# main_processor.net
KiCad netlist of a schematic drawn in Altium Designer
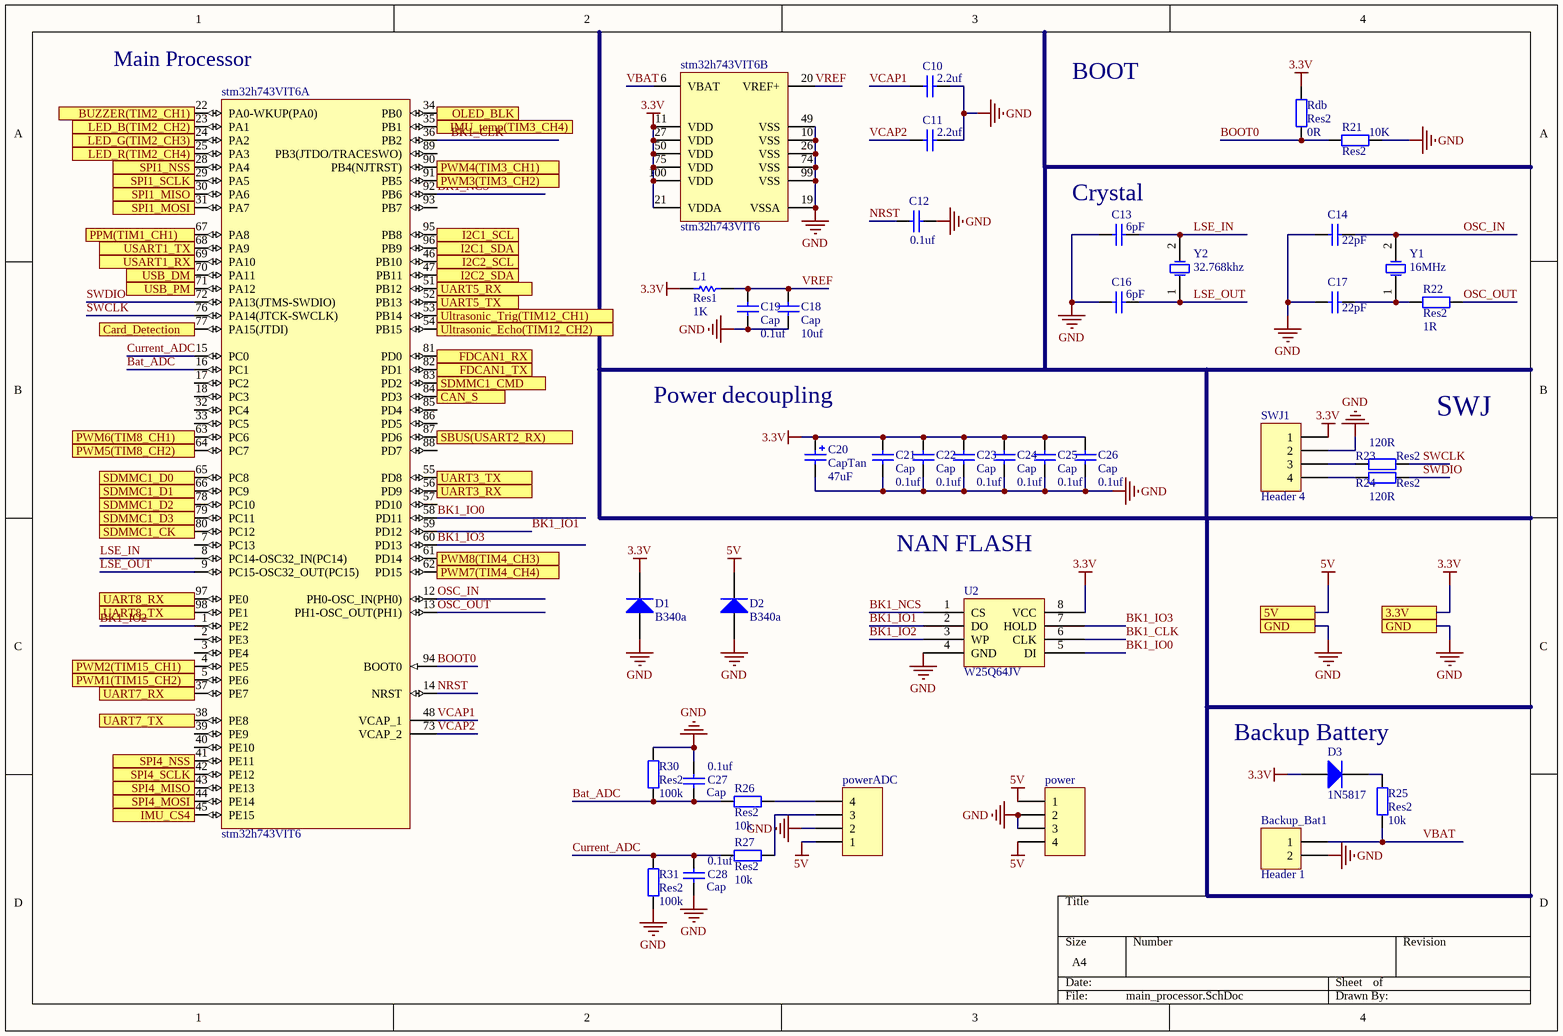
[diagram p0: main_processor.SchDoc]

(export (version "E")
  (design (tool "Eeschema 10.0.6"))
  (components
    (comp (ref "Backup_Bat1")
      (value "Header 1")
      (footprint "Battery-MS621")
      (description "Header, 2-Pin")
      (fields (field (name "PUBLISHER") "Altium Limited"))
      (libsource (lib "Miscellaneous Connectors") (part "Header 2"))
    )
    (comp (ref "C10")
      (value "2.2uf")
      (footprint "0603")
      (description "Capacitor")
      (fields (field (name "Comment") "Cap") (field (name "PUBLISHER") "Altium Limited"))
      (libsource (lib "Miscellaneous Devices") (part "Cap"))
    )
    (comp (ref "C11")
      (value "2.2uf")
      (footprint "0603")
      (description "Capacitor")
      (fields (field (name "Comment") "Cap") (field (name "PUBLISHER") "Altium Limited"))
      (libsource (lib "Miscellaneous Devices") (part "Cap"))
    )
    (comp (ref "C12")
      (value "0.1uf")
      (footprint "0603")
      (description "Capacitor")
      (fields (field (name "Comment") "Cap") (field (name "PUBLISHER") "Altium Limited"))
      (libsource (lib "Miscellaneous Devices") (part "Cap"))
    )
    (comp (ref "C13")
      (value "6pF")
      (footprint "0603")
      (description "Capacitor")
      (fields (field (name "Comment") "Cap") (field (name "PUBLISHER") "Altium Limited"))
      (libsource (lib "Miscellaneous Devices") (part "Cap"))
    )
    (comp (ref "C14")
      (value "22pF")
      (footprint "0603")
      (description "Capacitor")
      (fields (field (name "Comment") "Cap") (field (name "PUBLISHER") "Altium Limited"))
      (libsource (lib "Miscellaneous Devices") (part "Cap"))
    )
    (comp (ref "C16")
      (value "6pF")
      (footprint "0603")
      (description "Capacitor")
      (fields (field (name "Comment") "Cap") (field (name "PUBLISHER") "Altium Limited"))
      (libsource (lib "Miscellaneous Devices") (part "Cap"))
    )
    (comp (ref "C17")
      (value "22pF")
      (footprint "0603")
      (description "Capacitor")
      (fields (field (name "Comment") "Cap") (field (name "PUBLISHER") "Altium Limited"))
      (libsource (lib "Miscellaneous Devices") (part "Cap"))
    )
    (comp (ref "C18")
      (value "Cap")
      (footprint "0603")
      (description "Capacitor")
      (fields (field (name "ALTIUM_VALUE") "10uf") (field (name "PUBLISHER") "Altium Limited"))
      (libsource (lib "Miscellaneous Devices") (part "Cap"))
    )
    (comp (ref "C19")
      (value "Cap")
      (footprint "0603")
      (description "Capacitor")
      (fields (field (name "ALTIUM_VALUE") "0.1uf") (field (name "PUBLISHER") "Altium Limited"))
      (libsource (lib "Miscellaneous Devices") (part "Cap"))
    )
    (comp (ref "C20")
      (value "CapTan")
      (footprint "1206_P")
      (description "Polarized Capacitor (Axial)")
      (fields (field (name "ALTIUM_VALUE") "47uF") (field (name "PUBLISHER") "Altium Limited"))
      (libsource (lib "Miscellaneous Devices") (part "Cap Pol2"))
    )
    (comp (ref "C21")
      (value "Cap")
      (footprint "0603")
      (description "Capacitor")
      (fields (field (name "ALTIUM_VALUE") "0.1uf") (field (name "PUBLISHER") "Altium Limited"))
      (libsource (lib "Miscellaneous Devices") (part "Cap"))
    )
    (comp (ref "C22")
      (value "Cap")
      (footprint "0603")
      (description "Capacitor")
      (fields (field (name "ALTIUM_VALUE") "0.1uf") (field (name "PUBLISHER") "Altium Limited"))
      (libsource (lib "Miscellaneous Devices") (part "Cap"))
    )
    (comp (ref "C23")
      (value "Cap")
      (footprint "0603")
      (description "Capacitor")
      (fields (field (name "ALTIUM_VALUE") "0.1uf") (field (name "PUBLISHER") "Altium Limited"))
      (libsource (lib "Miscellaneous Devices") (part "Cap"))
    )
    (comp (ref "C24")
      (value "Cap")
      (footprint "0603")
      (description "Capacitor")
      (fields (field (name "ALTIUM_VALUE") "0.1uf") (field (name "PUBLISHER") "Altium Limited"))
      (libsource (lib "Miscellaneous Devices") (part "Cap"))
    )
    (comp (ref "C25")
      (value "Cap")
      (footprint "0603")
      (description "Capacitor")
      (fields (field (name "ALTIUM_VALUE") "0.1uf") (field (name "PUBLISHER") "Altium Limited"))
      (libsource (lib "Miscellaneous Devices") (part "Cap"))
    )
    (comp (ref "C26")
      (value "Cap")
      (footprint "0603")
      (description "Capacitor")
      (fields (field (name "ALTIUM_VALUE") "0.1uf") (field (name "PUBLISHER") "Altium Limited"))
      (libsource (lib "Miscellaneous Devices") (part "Cap"))
    )
    (comp (ref "C27")
      (value "Cap")
      (footprint "0603")
      (description "Capacitor")
      (fields (field (name "ALTIUM_VALUE") "0.1uf") (field (name "PUBLISHER") "Altium Limited"))
      (libsource (lib "Miscellaneous Devices") (part "Cap"))
    )
    (comp (ref "C28")
      (value "Cap")
      (footprint "0603")
      (description "Capacitor")
      (fields (field (name "ALTIUM_VALUE") "0.1uf") (field (name "PUBLISHER") "Altium Limited"))
      (libsource (lib "Miscellaneous Devices") (part "Cap"))
    )
    (comp (ref "D1")
      (value "B340a")
      (footprint "DO_214_AC")
      (description "Default Diode")
      (fields (field (name "PUBLISHER") "Altium Limited"))
      (libsource (lib "Miscellaneous Devices") (part "Diode"))
    )
    (comp (ref "D2")
      (value "B340a")
      (footprint "DO_214_AC")
      (description "Default Diode")
      (fields (field (name "PUBLISHER") "Altium Limited"))
      (libsource (lib "Miscellaneous Devices") (part "Diode"))
    )
    (comp (ref "D3")
      (value "1N5817")
      (footprint "SOD323")
      (description "Default Diode")
      (fields (field (name "PUBLISHER") "Altium Limited"))
      (libsource (lib "Miscellaneous Devices") (part "Diode"))
    )
    (comp (ref "L1")
      (value "Res1")
      (footprint "AXIAL-0.3")
      (description "Resistor")
      (fields (field (name "ALTIUM_VALUE") "1K") (field (name "PUBLISHER") "Altium Limited"))
      (libsource (lib "Miscellaneous Devices") (part "Res1"))
    )
    (comp (ref "power")
      (value "Header 2")
      (footprint "SH_1.25mm_LT_4P")
      (description "Header, 4-Pin")
      (fields (field (name "PUBLISHER") "Altium Limited"))
      (libsource (lib "") (part "Header 4_1"))
    )
    (comp (ref "powerADC")
      (value "Header 2")
      (footprint "SH_1.25mm_LT_4P")
      (description "Header, 4-Pin")
      (fields (field (name "PUBLISHER") "Altium Limited"))
      (libsource (lib "") (part "Header 4_2"))
    )
    (comp (ref "R21")
      (value "Res2")
      (footprint "0603")
      (description "Resistor")
      (fields (field (name "ALTIUM_VALUE") "10K") (field (name "PUBLISHER") "Altium Limited"))
      (libsource (lib "") (part "Res2_3"))
    )
    (comp (ref "R22")
      (value "Res2")
      (footprint "0603")
      (description "Resistor")
      (fields (field (name "ALTIUM_VALUE") "1R") (field (name "PUBLISHER") "Altium Limited"))
      (libsource (lib "Miscellaneous Devices") (part "Res2"))
    )
    (comp (ref "R23")
      (value "Res2")
      (footprint "0603")
      (description "Resistor")
      (fields (field (name "ALTIUM_VALUE") "120R") (field (name "PUBLISHER") "Altium Limited"))
      (libsource (lib "") (part "Res2_1"))
    )
    (comp (ref "R24")
      (value "Res2")
      (footprint "0603")
      (description "Resistor")
      (fields (field (name "ALTIUM_VALUE") "120R") (field (name "PUBLISHER") "Altium Limited"))
      (libsource (lib "") (part "Res2_1"))
    )
    (comp (ref "R25")
      (value "Res2")
      (footprint "0603")
      (description "Resistor")
      (fields (field (name "ALTIUM_VALUE") "10k") (field (name "PUBLISHER") "Altium Limited"))
      (libsource (lib "Miscellaneous Devices") (part "Res2"))
    )
    (comp (ref "R26")
      (value "Res2")
      (footprint "0603")
      (description "Resistor")
      (fields (field (name "ALTIUM_VALUE") "10k") (field (name "PUBLISHER") "Altium Limited"))
      (libsource (lib "") (part "Res2_1"))
    )
    (comp (ref "R27")
      (value "Res2")
      (footprint "0603")
      (description "Resistor")
      (fields (field (name "ALTIUM_VALUE") "10k") (field (name "PUBLISHER") "Altium Limited"))
      (libsource (lib "") (part "Res2_1"))
    )
    (comp (ref "R30")
      (value "Res2")
      (footprint "0603")
      (description "Resistor")
      (fields (field (name "ALTIUM_VALUE") "100k") (field (name "PUBLISHER") "Altium Limited"))
      (libsource (lib "Miscellaneous Devices") (part "Res2"))
    )
    (comp (ref "R31")
      (value "Res2")
      (footprint "0603")
      (description "Resistor")
      (fields (field (name "ALTIUM_VALUE") "100k") (field (name "PUBLISHER") "Altium Limited"))
      (libsource (lib "Miscellaneous Devices") (part "Res2"))
    )
    (comp (ref "Rdb")
      (value "Res2")
      (footprint "0603")
      (description "Resistor")
      (fields (field (name "ALTIUM_VALUE") "0R") (field (name "PUBLISHER") "Altium Limited"))
      (libsource (lib "") (part "Res2_2"))
    )
    (comp (ref "stm32h743VIT6")
      (value "stm32h743VIT6")
      (footprint "LQFP100-14x14mm")
      (libsource (lib "SchlibProcessor") (part "stm32h743VIT6"))
    )
    (comp (ref "SWJ1")
      (value "Header 4")
      (footprint "SH_1.25mm_LT_4P")
      (description "Header, 4-Pin")
      (fields (field (name "PUBLISHER") "Altium Limited"))
      (libsource (lib "Miscellaneous Connectors") (part "Header 4"))
    )
    (comp (ref "U2")
      (value "W25Q64JV")
      (footprint "W25Q SOP8")
      (libsource (lib "SchlibDevices") (part "W25Q64JV"))
    )
    (comp (ref "Y1")
      (value "16MHz")
      (footprint "Crystal_SMD_3225")
      (description "Crystal Oscillator")
      (fields (field (name "PUBLISHER") "Altium Limited"))
      (libsource (lib "Explorer STM32F407封装库") (part "XTAL"))
    )
    (comp (ref "Y2")
      (value "32.768khz")
      (footprint "FC135")
      (description "Crystal Oscillator")
      (fields (field (name "PUBLISHER") "Altium Limited"))
      (libsource (lib "Explorer STM32F407封装库") (part "XTAL"))
    )
  )
  (nets
    (net (code "1") (name "/BK1_CLK") (class "Default")
      (node (ref "U2") (pin "6") (pinfunction "CLK_6") (pintype "passive"))
      (node (ref "stm32h743VIT6") (pin "36") (pinfunction "PB2_36") (pintype "bidirectional"))
    )
    (net (code "2") (name "/BK1_IO0") (class "Default")
      (node (ref "U2") (pin "5") (pinfunction "DI_5") (pintype "passive"))
      (node (ref "stm32h743VIT6") (pin "58") (pinfunction "PD11_58") (pintype "bidirectional"))
    )
    (net (code "3") (name "/BK1_IO1") (class "Default")
      (node (ref "U2") (pin "2") (pinfunction "DO_2") (pintype "passive"))
      (node (ref "stm32h743VIT6") (pin "59") (pinfunction "PD12_59") (pintype "bidirectional"))
    )
    (net (code "4") (name "/BK1_IO2") (class "Default")
      (node (ref "U2") (pin "3") (pinfunction "WP_3") (pintype "passive"))
      (node (ref "stm32h743VIT6") (pin "1") (pinfunction "PE2_1") (pintype "bidirectional"))
    )
    (net (code "5") (name "/BK1_IO3") (class "Default")
      (node (ref "U2") (pin "7") (pinfunction "HOLD_7") (pintype "passive"))
      (node (ref "stm32h743VIT6") (pin "60") (pinfunction "PD13_60") (pintype "bidirectional"))
    )
    (net (code "6") (name "/BK1_NCS") (class "Default")
      (node (ref "U2") (pin "1") (pinfunction "CS_1") (pintype "passive"))
      (node (ref "stm32h743VIT6") (pin "92") (pinfunction "PB6_92") (pintype "bidirectional"))
    )
    (net (code "7") (name "/BOOT0") (class "Default")
      (node (ref "R21") (pin "1") (pinfunction "1_1") (pintype "passive"))
      (node (ref "Rdb") (pin "1") (pinfunction "1_1") (pintype "passive"))
      (node (ref "stm32h743VIT6") (pin "94") (pinfunction "BOOT0_94") (pintype "input"))
    )
    (net (code "8") (name "/BUZZER(TIM2_CH1)") (class "Default")
      (node (ref "stm32h743VIT6") (pin "22") (pinfunction "PA0-WKUP(PA0)_22") (pintype "bidirectional"))
    )
    (net (code "9") (name "/Bat_ADC") (class "Default")
      (node (ref "C27") (pin "1") (pinfunction "1_1") (pintype "passive"))
      (node (ref "R26") (pin "2") (pinfunction "2_2") (pintype "passive"))
      (node (ref "R30") (pin "2") (pinfunction "2_2") (pintype "passive"))
      (node (ref "stm32h743VIT6") (pin "16") (pinfunction "PC1_16") (pintype "bidirectional"))
    )
    (net (code "10") (name "/CAN_S") (class "Default")
      (node (ref "stm32h743VIT6") (pin "84") (pinfunction "PD3_84") (pintype "bidirectional"))
    )
    (net (code "11") (name "/Card_Detection") (class "Default")
      (node (ref "stm32h743VIT6") (pin "77") (pinfunction "PA15(JTDI)_77") (pintype "bidirectional"))
    )
    (net (code "12") (name "/Current_ADC") (class "Default")
      (node (ref "C28") (pin "2") (pinfunction "2_2") (pintype "passive"))
      (node (ref "R27") (pin "2") (pinfunction "2_2") (pintype "passive"))
      (node (ref "R31") (pin "1") (pinfunction "1_1") (pintype "passive"))
      (node (ref "stm32h743VIT6") (pin "15") (pinfunction "PC0_15") (pintype "bidirectional"))
    )
    (net (code "13") (name "/FDCAN1_RX") (class "Default")
      (node (ref "stm32h743VIT6") (pin "81") (pinfunction "PD0_81") (pintype "bidirectional"))
    )
    (net (code "14") (name "/FDCAN1_TX") (class "Default")
      (node (ref "stm32h743VIT6") (pin "82") (pinfunction "PD1_82") (pintype "bidirectional"))
    )
    (net (code "15") (name "/I2C1_SCL") (class "Default")
      (node (ref "stm32h743VIT6") (pin "95") (pinfunction "PB8_95") (pintype "bidirectional"))
    )
    (net (code "16") (name "/I2C1_SDA") (class "Default")
      (node (ref "stm32h743VIT6") (pin "96") (pinfunction "PB9_96") (pintype "bidirectional"))
    )
    (net (code "17") (name "/I2C2_SCL") (class "Default")
      (node (ref "stm32h743VIT6") (pin "46") (pinfunction "PB10_46") (pintype "bidirectional"))
    )
    (net (code "18") (name "/I2C2_SDA") (class "Default")
      (node (ref "stm32h743VIT6") (pin "47") (pinfunction "PB11_47") (pintype "bidirectional"))
    )
    (net (code "19") (name "/IMU_CS4") (class "Default")
      (node (ref "stm32h743VIT6") (pin "45") (pinfunction "PE15_45") (pintype "bidirectional"))
    )
    (net (code "20") (name "/IMU_temp(TIM3_CH4)") (class "Default")
      (node (ref "stm32h743VIT6") (pin "35") (pinfunction "PB1_35") (pintype "bidirectional"))
    )
    (net (code "21") (name "/LED_B(TIM2_CH2)") (class "Default")
      (node (ref "stm32h743VIT6") (pin "23") (pinfunction "PA1_23") (pintype "bidirectional"))
    )
    (net (code "22") (name "/LED_G(TIM2_CH3)") (class "Default")
      (node (ref "stm32h743VIT6") (pin "24") (pinfunction "PA2_24") (pintype "bidirectional"))
    )
    (net (code "23") (name "/LED_R(TIM2_CH4)") (class "Default")
      (node (ref "stm32h743VIT6") (pin "25") (pinfunction "PA3_25") (pintype "bidirectional"))
    )
    (net (code "24") (name "/LSE_IN") (class "Default")
      (node (ref "C13") (pin "2") (pinfunction "2_2") (pintype "passive"))
      (node (ref "Y2") (pin "2") (pinfunction "OSC2_2") (pintype "passive"))
      (node (ref "stm32h743VIT6") (pin "8") (pinfunction "PC14-OSC32_IN(PC14)_8") (pintype "bidirectional"))
    )
    (net (code "25") (name "/LSE_OUT") (class "Default")
      (node (ref "C16") (pin "2") (pinfunction "2_2") (pintype "passive"))
      (node (ref "Y2") (pin "1") (pinfunction "OSC1_1") (pintype "passive"))
      (node (ref "stm32h743VIT6") (pin "9") (pinfunction "PC15-OSC32_OUT(PC15)_9") (pintype "bidirectional"))
    )
    (net (code "26") (name "/NRST") (class "Default")
      (node (ref "C12") (pin "2") (pinfunction "2_2") (pintype "passive"))
      (node (ref "stm32h743VIT6") (pin "14") (pinfunction "NRST_14") (pintype "bidirectional"))
    )
    (net (code "27") (name "/OLED_BLK") (class "Default")
      (node (ref "stm32h743VIT6") (pin "34") (pinfunction "PB0_34") (pintype "bidirectional"))
    )
    (net (code "28") (name "/OSC_IN") (class "Default")
      (node (ref "C14") (pin "2") (pinfunction "2_2") (pintype "passive"))
      (node (ref "Y1") (pin "2") (pinfunction "OSC2_2") (pintype "passive"))
      (node (ref "stm32h743VIT6") (pin "12") (pinfunction "PH0-OSC_IN(PH0)_12") (pintype "bidirectional"))
    )
    (net (code "29") (name "/OSC_OUT") (class "Default")
      (node (ref "R22") (pin "1") (pinfunction "1_1") (pintype "passive"))
      (node (ref "stm32h743VIT6") (pin "13") (pinfunction "PH1-OSC_OUT(PH1)_13") (pintype "bidirectional"))
    )
    (net (code "30") (name "/PPM(TIM1_CH1)") (class "Default")
      (node (ref "stm32h743VIT6") (pin "67") (pinfunction "PA8_67") (pintype "bidirectional"))
    )
    (net (code "31") (name "/PWM1(TIM15_CH2)") (class "Default")
      (node (ref "stm32h743VIT6") (pin "5") (pinfunction "PE6_5") (pintype "bidirectional"))
    )
    (net (code "32") (name "/PWM2(TIM15_CH1)") (class "Default")
      (node (ref "stm32h743VIT6") (pin "4") (pinfunction "PE5_4") (pintype "bidirectional"))
    )
    (net (code "33") (name "/PWM3(TIM3_CH2)") (class "Default")
      (node (ref "stm32h743VIT6") (pin "91") (pinfunction "PB5_91") (pintype "bidirectional"))
    )
    (net (code "34") (name "/PWM4(TIM3_CH1)") (class "Default")
      (node (ref "stm32h743VIT6") (pin "90") (pinfunction "PB4(NJTRST)_90") (pintype "bidirectional"))
    )
    (net (code "35") (name "/PWM5(TIM8_CH2)") (class "Default")
      (node (ref "stm32h743VIT6") (pin "64") (pinfunction "PC7_64") (pintype "bidirectional"))
    )
    (net (code "36") (name "/PWM6(TIM8_CH1)") (class "Default")
      (node (ref "stm32h743VIT6") (pin "63") (pinfunction "PC6_63") (pintype "bidirectional"))
    )
    (net (code "37") (name "/PWM7(TIM4_CH4)") (class "Default")
      (node (ref "stm32h743VIT6") (pin "62") (pinfunction "PD15_62") (pintype "bidirectional"))
    )
    (net (code "38") (name "/PWM8(TIM4_CH3)") (class "Default")
      (node (ref "stm32h743VIT6") (pin "61") (pinfunction "PD14_61") (pintype "bidirectional"))
    )
    (net (code "39") (name "/SBUS(USART2_RX)") (class "Default")
      (node (ref "stm32h743VIT6") (pin "87") (pinfunction "PD6_87") (pintype "bidirectional"))
    )
    (net (code "40") (name "/SDMMC1_CK") (class "Default")
      (node (ref "stm32h743VIT6") (pin "80") (pinfunction "PC12_80") (pintype "bidirectional"))
    )
    (net (code "41") (name "/SDMMC1_CMD") (class "Default")
      (node (ref "stm32h743VIT6") (pin "83") (pinfunction "PD2_83") (pintype "bidirectional"))
    )
    (net (code "42") (name "/SDMMC1_D0") (class "Default")
      (node (ref "stm32h743VIT6") (pin "65") (pinfunction "PC8_65") (pintype "bidirectional"))
    )
    (net (code "43") (name "/SDMMC1_D1") (class "Default")
      (node (ref "stm32h743VIT6") (pin "66") (pinfunction "PC9_66") (pintype "bidirectional"))
    )
    (net (code "44") (name "/SDMMC1_D2") (class "Default")
      (node (ref "stm32h743VIT6") (pin "78") (pinfunction "PC10_78") (pintype "bidirectional"))
    )
    (net (code "45") (name "/SDMMC1_D3") (class "Default")
      (node (ref "stm32h743VIT6") (pin "79") (pinfunction "PC11_79") (pintype "bidirectional"))
    )
    (net (code "46") (name "/SPI1_MISO") (class "Default")
      (node (ref "stm32h743VIT6") (pin "30") (pinfunction "PA6_30") (pintype "bidirectional"))
    )
    (net (code "47") (name "/SPI1_MOSI") (class "Default")
      (node (ref "stm32h743VIT6") (pin "31") (pinfunction "PA7_31") (pintype "bidirectional"))
    )
    (net (code "48") (name "/SPI1_NSS") (class "Default")
      (node (ref "stm32h743VIT6") (pin "28") (pinfunction "PA4_28") (pintype "bidirectional"))
    )
    (net (code "49") (name "/SPI1_SCLK") (class "Default")
      (node (ref "stm32h743VIT6") (pin "29") (pinfunction "PA5_29") (pintype "bidirectional"))
    )
    (net (code "50") (name "/SPI4_MISO") (class "Default")
      (node (ref "stm32h743VIT6") (pin "43") (pinfunction "PE13_43") (pintype "bidirectional"))
    )
    (net (code "51") (name "/SPI4_MOSI") (class "Default")
      (node (ref "stm32h743VIT6") (pin "44") (pinfunction "PE14_44") (pintype "bidirectional"))
    )
    (net (code "52") (name "/SPI4_NSS") (class "Default")
      (node (ref "stm32h743VIT6") (pin "41") (pinfunction "PE11_41") (pintype "bidirectional"))
    )
    (net (code "53") (name "/SPI4_SCLK") (class "Default")
      (node (ref "stm32h743VIT6") (pin "42") (pinfunction "PE12_42") (pintype "bidirectional"))
    )
    (net (code "54") (name "/SWCLK") (class "Default")
      (node (ref "R23") (pin "1") (pinfunction "1_1") (pintype "passive"))
      (node (ref "stm32h743VIT6") (pin "76") (pinfunction "PA14(JTCK-SWCLK)_76") (pintype "bidirectional"))
    )
    (net (code "55") (name "/SWDIO") (class "Default")
      (node (ref "R24") (pin "1") (pinfunction "1_1") (pintype "passive"))
      (node (ref "stm32h743VIT6") (pin "72") (pinfunction "PA13(JTMS-SWDIO)_72") (pintype "bidirectional"))
    )
    (net (code "56") (name "/UART3_RX") (class "Default")
      (node (ref "stm32h743VIT6") (pin "56") (pinfunction "PD9_56") (pintype "bidirectional"))
    )
    (net (code "57") (name "/UART3_TX") (class "Default")
      (node (ref "stm32h743VIT6") (pin "55") (pinfunction "PD8_55") (pintype "bidirectional"))
    )
    (net (code "58") (name "/UART5_RX") (class "Default")
      (node (ref "stm32h743VIT6") (pin "51") (pinfunction "PB12_51") (pintype "bidirectional"))
    )
    (net (code "59") (name "/UART5_TX") (class "Default")
      (node (ref "stm32h743VIT6") (pin "52") (pinfunction "PB13_52") (pintype "bidirectional"))
    )
    (net (code "60") (name "/UART7_RX") (class "Default")
      (node (ref "stm32h743VIT6") (pin "37") (pinfunction "PE7_37") (pintype "bidirectional"))
    )
    (net (code "61") (name "/UART7_TX") (class "Default")
      (node (ref "stm32h743VIT6") (pin "38") (pinfunction "PE8_38") (pintype "bidirectional"))
    )
    (net (code "62") (name "/UART8_RX") (class "Default")
      (node (ref "stm32h743VIT6") (pin "97") (pinfunction "PE0_97") (pintype "bidirectional"))
    )
    (net (code "63") (name "/UART8_TX") (class "Default")
      (node (ref "stm32h743VIT6") (pin "98") (pinfunction "PE1_98") (pintype "bidirectional"))
    )
    (net (code "64") (name "/USART1_RX") (class "Default")
      (node (ref "stm32h743VIT6") (pin "69") (pinfunction "PA10_69") (pintype "bidirectional"))
    )
    (net (code "65") (name "/USART1_TX") (class "Default")
      (node (ref "stm32h743VIT6") (pin "68") (pinfunction "PA9_68") (pintype "bidirectional"))
    )
    (net (code "66") (name "/USB_DM") (class "Default")
      (node (ref "stm32h743VIT6") (pin "70") (pinfunction "PA11_70") (pintype "bidirectional"))
    )
    (net (code "67") (name "/USB_PM") (class "Default")
      (node (ref "stm32h743VIT6") (pin "71") (pinfunction "PA12_71") (pintype "bidirectional"))
    )
    (net (code "68") (name "/Ultrasonic_Echo(TIM12_CH2)") (class "Default")
      (node (ref "stm32h743VIT6") (pin "54") (pinfunction "PB15_54") (pintype "bidirectional"))
    )
    (net (code "69") (name "/Ultrasonic_Trig(TIM12_CH1)") (class "Default")
      (node (ref "stm32h743VIT6") (pin "53") (pinfunction "PB14_53") (pintype "bidirectional"))
    )
    (net (code "70") (name "/VBAT") (class "Default")
      (node (ref "Backup_Bat1") (pin "1") (pinfunction "1_1") (pintype "passive"))
      (node (ref "R25") (pin "2") (pinfunction "2_2") (pintype "passive"))
      (node (ref "stm32h743VIT6") (pin "6") (pinfunction "VBAT_6") (pintype "power_in"))
    )
    (net (code "71") (name "/VCAP1") (class "Default")
      (node (ref "C10") (pin "1") (pinfunction "1_1") (pintype "passive"))
      (node (ref "stm32h743VIT6") (pin "48") (pinfunction "VCAP_1_48") (pintype "power_in"))
    )
    (net (code "72") (name "/VCAP2") (class "Default")
      (node (ref "C11") (pin "1") (pinfunction "1_1") (pintype "passive"))
      (node (ref "stm32h743VIT6") (pin "73") (pinfunction "VCAP_2_73") (pintype "power_in"))
    )
    (net (code "73") (name "/VREF") (class "Default")
      (node (ref "C18") (pin "2") (pinfunction "2_2") (pintype "passive"))
      (node (ref "C19") (pin "2") (pinfunction "2_2") (pintype "passive"))
      (node (ref "L1") (pin "2") (pinfunction "2_2") (pintype "passive"))
      (node (ref "stm32h743VIT6") (pin "20") (pinfunction "VREF+_20") (pintype "power_in"))
    )
    (net (code "74") (name "3.3V") (class "Default")
      (node (ref "C20") (pin "1") (pinfunction "1_1") (pintype "passive"))
      (node (ref "C21") (pin "2") (pinfunction "2_2") (pintype "passive"))
      (node (ref "C22") (pin "2") (pinfunction "2_2") (pintype "passive"))
      (node (ref "C23") (pin "2") (pinfunction "2_2") (pintype "passive"))
      (node (ref "C24") (pin "2") (pinfunction "2_2") (pintype "passive"))
      (node (ref "C25") (pin "2") (pinfunction "2_2") (pintype "passive"))
      (node (ref "C26") (pin "2") (pinfunction "2_2") (pintype "passive"))
      (node (ref "D1") (pin "2") (pinfunction "K_2") (pintype "passive"))
      (node (ref "D3") (pin "1") (pinfunction "A_1") (pintype "passive"))
      (node (ref "L1") (pin "1") (pinfunction "1_1") (pintype "passive"))
      (node (ref "Rdb") (pin "2") (pinfunction "2_2") (pintype "passive"))
      (node (ref "SWJ1") (pin "1") (pinfunction "1_1") (pintype "passive"))
      (node (ref "U2") (pin "8") (pinfunction "VCC_8") (pintype "passive"))
      (node (ref "stm32h743VIT6") (pin "100") (pinfunction "VDD_100") (pintype "power_in"))
      (node (ref "stm32h743VIT6") (pin "11") (pinfunction "VDD_11") (pintype "power_in"))
      (node (ref "stm32h743VIT6") (pin "21") (pinfunction "VDDA_21") (pintype "power_in"))
      (node (ref "stm32h743VIT6") (pin "27") (pinfunction "VDD_27") (pintype "power_in"))
      (node (ref "stm32h743VIT6") (pin "50") (pinfunction "VDD_50") (pintype "power_in"))
      (node (ref "stm32h743VIT6") (pin "75") (pinfunction "VDD_75") (pintype "power_in"))
    )
    (net (code "75") (name "5V") (class "Default")
      (node (ref "D2") (pin "2") (pinfunction "K_2") (pintype "passive"))
      (node (ref "power") (pin "1") (pinfunction "1_1") (pintype "passive"))
      (node (ref "power") (pin "4") (pinfunction "4_4") (pintype "passive"))
      (node (ref "powerADC") (pin "1") (pinfunction "1_1") (pintype "passive"))
    )
    (net (code "76") (name "GND") (class "Default")
      (node (ref "Backup_Bat1") (pin "2") (pinfunction "2_2") (pintype "passive"))
      (node (ref "C10") (pin "2") (pinfunction "2_2") (pintype "passive"))
      (node (ref "C11") (pin "2") (pinfunction "2_2") (pintype "passive"))
      (node (ref "C12") (pin "1") (pinfunction "1_1") (pintype "passive"))
      (node (ref "C13") (pin "1") (pinfunction "1_1") (pintype "passive"))
      (node (ref "C14") (pin "1") (pinfunction "1_1") (pintype "passive"))
      (node (ref "C16") (pin "1") (pinfunction "1_1") (pintype "passive"))
      (node (ref "C17") (pin "1") (pinfunction "1_1") (pintype "passive"))
      (node (ref "C18") (pin "1") (pinfunction "1_1") (pintype "passive"))
      (node (ref "C19") (pin "1") (pinfunction "1_1") (pintype "passive"))
      (node (ref "C20") (pin "2") (pinfunction "2_2") (pintype "passive"))
      (node (ref "C21") (pin "1") (pinfunction "1_1") (pintype "passive"))
      (node (ref "C22") (pin "1") (pinfunction "1_1") (pintype "passive"))
      (node (ref "C23") (pin "1") (pinfunction "1_1") (pintype "passive"))
      (node (ref "C24") (pin "1") (pinfunction "1_1") (pintype "passive"))
      (node (ref "C25") (pin "1") (pinfunction "1_1") (pintype "passive"))
      (node (ref "C26") (pin "1") (pinfunction "1_1") (pintype "passive"))
      (node (ref "C27") (pin "2") (pinfunction "2_2") (pintype "passive"))
      (node (ref "C28") (pin "1") (pinfunction "1_1") (pintype "passive"))
      (node (ref "D1") (pin "1") (pinfunction "A_1") (pintype "passive"))
      (node (ref "D2") (pin "1") (pinfunction "A_1") (pintype "passive"))
      (node (ref "R21") (pin "2") (pinfunction "2_2") (pintype "passive"))
      (node (ref "R30") (pin "1") (pinfunction "1_1") (pintype "passive"))
      (node (ref "R31") (pin "2") (pinfunction "2_2") (pintype "passive"))
      (node (ref "SWJ1") (pin "2") (pinfunction "2_2") (pintype "passive"))
      (node (ref "U2") (pin "4") (pinfunction "GND_4") (pintype "passive"))
      (node (ref "power") (pin "2") (pinfunction "2_2") (pintype "passive"))
      (node (ref "power") (pin "3") (pinfunction "3_3") (pintype "passive"))
      (node (ref "powerADC") (pin "2") (pinfunction "2_2") (pintype "passive"))
      (node (ref "stm32h743VIT6") (pin "10") (pinfunction "VSS_10") (pintype "power_in"))
      (node (ref "stm32h743VIT6") (pin "19") (pinfunction "VSSA_19") (pintype "power_in"))
      (node (ref "stm32h743VIT6") (pin "26") (pinfunction "VSS_26") (pintype "power_in"))
      (node (ref "stm32h743VIT6") (pin "49") (pinfunction "VSS_49") (pintype "power_in"))
      (node (ref "stm32h743VIT6") (pin "74") (pinfunction "VSS_74") (pintype "power_in"))
      (node (ref "stm32h743VIT6") (pin "99") (pinfunction "VSS_99") (pintype "power_in"))
    )
    (net (code "77") (name "Net-(D3-K)") (class "Default")
      (node (ref "D3") (pin "2") (pinfunction "K_2") (pintype "passive"))
      (node (ref "R25") (pin "1") (pinfunction "1_1") (pintype "passive"))
    )
    (net (code "78") (name "Net-(R23-Pad2)") (class "Default")
      (node (ref "R23") (pin "2") (pinfunction "2_2") (pintype "passive"))
      (node (ref "SWJ1") (pin "3") (pinfunction "3_3") (pintype "passive"))
    )
    (net (code "79") (name "Net-(R24-Pad2)") (class "Default")
      (node (ref "R24") (pin "2") (pinfunction "2_2") (pintype "passive"))
      (node (ref "SWJ1") (pin "4") (pinfunction "4_4") (pintype "passive"))
    )
    (net (code "80") (name "Net-(R26-Pad1)") (class "Default")
      (node (ref "R26") (pin "1") (pinfunction "1_1") (pintype "passive"))
      (node (ref "powerADC") (pin "4") (pinfunction "4_4") (pintype "passive"))
    )
    (net (code "81") (name "Net-(R27-Pad1)") (class "Default")
      (node (ref "R27") (pin "1") (pinfunction "1_1") (pintype "passive"))
      (node (ref "powerADC") (pin "3") (pinfunction "3_3") (pintype "passive"))
    )
    (net (code "82") (name "Net-(Y1-OSC1)") (class "Default")
      (node (ref "C17") (pin "2") (pinfunction "2_2") (pintype "passive"))
      (node (ref "R22") (pin "2") (pinfunction "2_2") (pintype "passive"))
      (node (ref "Y1") (pin "1") (pinfunction "OSC1_1") (pintype "passive"))
    )
    (net (code "83") (name "unconnected-(stm32h743VIT6A-PB3(JTDO{slash}TRACESWO)-Pad89)") (class "Default")
      (node (ref "stm32h743VIT6") (pin "89") (pinfunction "PB3(JTDO/TRACESWO)_89") (pintype "bidirectional"))
    )
    (net (code "84") (name "unconnected-(stm32h743VIT6A-PB7-Pad93)") (class "Default")
      (node (ref "stm32h743VIT6") (pin "93") (pinfunction "PB7_93") (pintype "bidirectional"))
    )
    (net (code "85") (name "unconnected-(stm32h743VIT6A-PC2-Pad17)") (class "Default")
      (node (ref "stm32h743VIT6") (pin "17") (pinfunction "PC2_17") (pintype "bidirectional"))
    )
    (net (code "86") (name "unconnected-(stm32h743VIT6A-PC3-Pad18)") (class "Default")
      (node (ref "stm32h743VIT6") (pin "18") (pinfunction "PC3_18") (pintype "bidirectional"))
    )
    (net (code "87") (name "unconnected-(stm32h743VIT6A-PC4-Pad32)") (class "Default")
      (node (ref "stm32h743VIT6") (pin "32") (pinfunction "PC4_32") (pintype "bidirectional"))
    )
    (net (code "88") (name "unconnected-(stm32h743VIT6A-PC5-Pad33)") (class "Default")
      (node (ref "stm32h743VIT6") (pin "33") (pinfunction "PC5_33") (pintype "bidirectional"))
    )
    (net (code "89") (name "unconnected-(stm32h743VIT6A-PC13-Pad7)") (class "Default")
      (node (ref "stm32h743VIT6") (pin "7") (pinfunction "PC13_7") (pintype "bidirectional"))
    )
    (net (code "90") (name "unconnected-(stm32h743VIT6A-PD4-Pad85)") (class "Default")
      (node (ref "stm32h743VIT6") (pin "85") (pinfunction "PD4_85") (pintype "bidirectional"))
    )
    (net (code "91") (name "unconnected-(stm32h743VIT6A-PD5-Pad86)") (class "Default")
      (node (ref "stm32h743VIT6") (pin "86") (pinfunction "PD5_86") (pintype "bidirectional"))
    )
    (net (code "92") (name "unconnected-(stm32h743VIT6A-PD7-Pad88)") (class "Default")
      (node (ref "stm32h743VIT6") (pin "88") (pinfunction "PD7_88") (pintype "bidirectional"))
    )
    (net (code "93") (name "unconnected-(stm32h743VIT6A-PD10-Pad57)") (class "Default")
      (node (ref "stm32h743VIT6") (pin "57") (pinfunction "PD10_57") (pintype "bidirectional"))
    )
    (net (code "94") (name "unconnected-(stm32h743VIT6A-PE3-Pad2)") (class "Default")
      (node (ref "stm32h743VIT6") (pin "2") (pinfunction "PE3_2") (pintype "bidirectional"))
    )
    (net (code "95") (name "unconnected-(stm32h743VIT6A-PE4-Pad3)") (class "Default")
      (node (ref "stm32h743VIT6") (pin "3") (pinfunction "PE4_3") (pintype "bidirectional"))
    )
    (net (code "96") (name "unconnected-(stm32h743VIT6A-PE9-Pad39)") (class "Default")
      (node (ref "stm32h743VIT6") (pin "39") (pinfunction "PE9_39") (pintype "bidirectional"))
    )
    (net (code "97") (name "unconnected-(stm32h743VIT6A-PE10-Pad40)") (class "Default")
      (node (ref "stm32h743VIT6") (pin "40") (pinfunction "PE10_40") (pintype "bidirectional"))
    )
  )
)
